# Gate-drive.net
KiCad netlist of a schematic drawn in Altium Designer
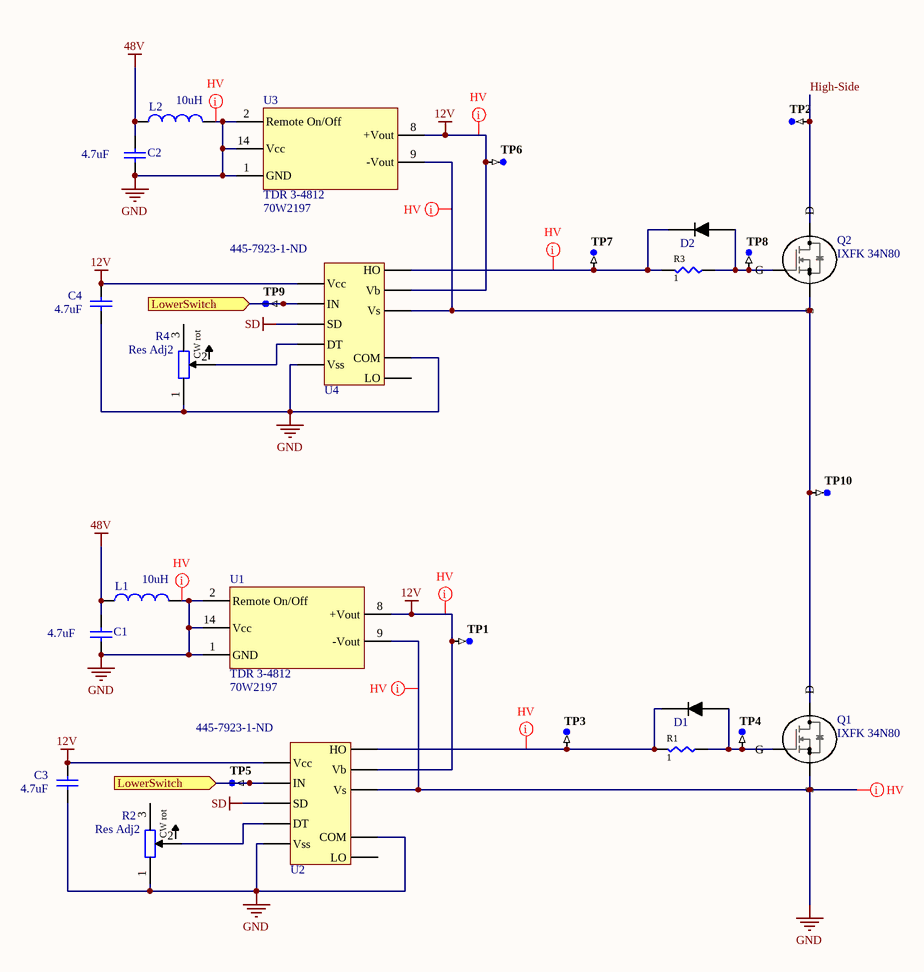
[diagram p0: Gate-drive.SchDoc]

(export (version "E")
  (design (tool "Eeschema 10.0.6"))
  (components
    (comp (ref "C1")
      (value "4.7uF")
      (footprint "C4532")
      (description "Capacitor")
      (fields
        (field (name "MANUFACTURER") "TDK")
        (field (name "MANUFACTURER PART NUMBER") "CGA8N3X7S2A475K230KB")
        (field (name "PUBLISHER") "Altium Limited")
      )
      (libsource (lib "T-Type Converter") (part "Cap"))
    )
    (comp (ref "C2")
      (value "4.7uF")
      (footprint "C4532")
      (description "Capacitor")
      (fields
        (field (name "MANUFACTURER") "TDK")
        (field (name "MANUFACTURER PART NUMBER") "CGA8N3X7S2A475K230KB")
        (field (name "PUBLISHER") "Altium Limited")
      )
      (libsource (lib "T-Type Converter") (part "Cap"))
    )
    (comp (ref "C3")
      (value "4.7uF")
      (footprint "C4532")
      (description "Capacitor")
      (fields
        (field (name "SUPPLIER PART NUMBER 1") "445-7923-1-ND")
        (field (name "MANUFACTURER") "TDK")
        (field (name "MANUFACTURER PART NUMBER") "CGA8N3X7S2A475K230KB")
        (field (name "PUBLISHER") "Altium Limited")
      )
      (libsource (lib "T-Type Converter") (part "Cap"))
    )
    (comp (ref "C4")
      (value "4.7uF")
      (footprint "C4532")
      (description "Capacitor")
      (fields
        (field (name "SUPPLIER PART NUMBER 1") "445-7923-1-ND")
        (field (name "MANUFACTURER") "TDK")
        (field (name "MANUFACTURER PART NUMBER") "CGA8N3X7S2A475K230KB")
        (field (name "PUBLISHER") "Altium Limited")
      )
      (libsource (lib "T-Type Converter") (part "Cap"))
    )
    (comp (ref "D1")
      (value "1N4148")
      (footprint "DO-35_02")
      (description "Diode")
      (fields (field (name "MANUFACTURER") "Fairchild Semiconductor"))
      (libsource (lib "T-Type Converter") (part "1N4148"))
    )
    (comp (ref "D2")
      (value "1N4148")
      (footprint "DO-35_02")
      (description "Diode")
      (fields (field (name "MANUFACTURER") "Fairchild Semiconductor"))
      (libsource (lib "T-Type Converter") (part "1N4148"))
    )
    (comp (ref "L1")
      (value "10uH")
      (footprint "TCK-047")
      (description "Inductor")
      (fields (field (name "PUBLISHER") "Altium Limited"))
      (libsource (lib "Miscellaneous Devices") (part "Inductor"))
    )
    (comp (ref "L2")
      (value "10uH")
      (footprint "TCK-047")
      (description "Inductor")
      (fields (field (name "PUBLISHER") "Altium Limited"))
      (libsource (lib "Miscellaneous Devices") (part "Inductor"))
    )
    (comp (ref "Q1")
      (value "IXFK 34N80")
      (footprint "TO-264 AA")
      (description "MOSFET 34A")
      (fields (field (name "MANUFACTURER") "IXYS") (field (name "MANUFACTURER PART NUMBER") "IXFK34N80"))
      (libsource (lib "T-Type Converter") (part "IXFK 34N80"))
    )
    (comp (ref "Q2")
      (value "IXFK 34N80")
      (footprint "TO-264 AA")
      (description "MOSFET 34A")
      (fields (field (name "MANUFACTURER") "IXYS") (field (name "MANUFACTURER PART NUMBER") "IXFK34N80"))
      (libsource (lib "T-Type Converter") (part "IXFK 34N80"))
    )
    (comp (ref "R1")
      (value "1")
      (footprint "R_1206")
      (description "RES SMD 1% 1/4W 1206")
      (fields
        (field (name "MANUFACTURER") "Panasonic Electronic Components")
        (field (name "MANUFACTURER PART NUMBER") "ERJ-8ENF9101V")
      )
      (libsource (lib "T-Type Converter") (part "RES_SMD1"))
    )
    (comp (ref "R2")
      (value "Res Adj2")
      (footprint "CT-6EP")
      (description "Variable Resistor")
      (fields
        (field (name "MANUFACTURER") "Nidec Copal")
        (field (name "MANUFACTURER PART NUMBER") "CT-6EP103")
        (field (name "PUBLISHER") "Altium Limited")
      )
      (libsource (lib "T-Type Converter") (part "Res Adj2"))
    )
    (comp (ref "R3")
      (value "1")
      (footprint "R_1206")
      (description "RES SMD 1% 1/4W 1206")
      (fields
        (field (name "MANUFACTURER") "Panasonic Electronic Components")
        (field (name "MANUFACTURER PART NUMBER") "ERJ-8ENF9101V")
      )
      (libsource (lib "T-Type Converter") (part "RES_SMD1"))
    )
    (comp (ref "R4")
      (value "Res Adj2")
      (footprint "CT-6EP")
      (description "Variable Resistor")
      (fields
        (field (name "MANUFACTURER") "Nidec Copal")
        (field (name "MANUFACTURER PART NUMBER") "CT-6EP103")
        (field (name "PUBLISHER") "Altium Limited")
      )
      (libsource (lib "T-Type Converter") (part "Res Adj2"))
    )
    (comp (ref "TP1")
      (value "TP-SM-C-100")
      (footprint "TP-SM-C-100")
      (description "Test Point, Surface Mount, Circular, Pad Diameter 1 mm")
      (fields (field (name "MANUFACTURER") "No Vendor"))
      (libsource (lib "Altium Content Vault") (part "CMP-0484-00002-2"))
    )
    (comp (ref "TP2")
      (value "TP-SM-C-100")
      (footprint "TP-SM-C-100")
      (description "Test Point, Surface Mount, Circular, Pad Diameter 1 mm")
      (fields (field (name "MANUFACTURER") "No Vendor"))
      (libsource (lib "Altium Content Vault") (part "CMP-0484-00002-2"))
    )
    (comp (ref "TP3")
      (value "TP-SM-C-100")
      (footprint "TP-SM-C-100")
      (description "Test Point, Surface Mount, Circular, Pad Diameter 1 mm")
      (fields (field (name "MANUFACTURER") "No Vendor"))
      (libsource (lib "Altium Content Vault") (part "CMP-0484-00002-2"))
    )
    (comp (ref "TP4")
      (value "TP-SM-C-100")
      (footprint "TP-SM-C-100")
      (description "Test Point, Surface Mount, Circular, Pad Diameter 1 mm")
      (fields (field (name "MANUFACTURER") "No Vendor"))
      (libsource (lib "Altium Content Vault") (part "CMP-0484-00002-2"))
    )
    (comp (ref "TP5")
      (value "TP-SM-C-100")
      (footprint "TP-SM-C-100")
      (description "Test Point, Surface Mount, Circular, Pad Diameter 1 mm")
      (fields (field (name "MANUFACTURER") "No Vendor"))
      (libsource (lib "Altium Content Vault") (part "CMP-0484-00002-2"))
    )
    (comp (ref "TP6")
      (value "TP-SM-C-100")
      (footprint "TP-SM-C-100")
      (description "Test Point, Surface Mount, Circular, Pad Diameter 1 mm")
      (fields (field (name "MANUFACTURER") "No Vendor"))
      (libsource (lib "Altium Content Vault") (part "CMP-0484-00002-2"))
    )
    (comp (ref "TP7")
      (value "TP-SM-C-100")
      (footprint "TP-SM-C-100")
      (description "Test Point, Surface Mount, Circular, Pad Diameter 1 mm")
      (fields (field (name "MANUFACTURER") "No Vendor"))
      (libsource (lib "Altium Content Vault") (part "CMP-0484-00002-2"))
    )
    (comp (ref "TP8")
      (value "TP-SM-C-100")
      (footprint "TP-SM-C-100")
      (description "Test Point, Surface Mount, Circular, Pad Diameter 1 mm")
      (fields (field (name "MANUFACTURER") "No Vendor"))
      (libsource (lib "Altium Content Vault") (part "CMP-0484-00002-2"))
    )
    (comp (ref "TP9")
      (value "TP-SM-C-100")
      (footprint "TP-SM-C-100")
      (description "Test Point, Surface Mount, Circular, Pad Diameter 1 mm")
      (fields (field (name "MANUFACTURER") "No Vendor"))
      (libsource (lib "Altium Content Vault") (part "CMP-0484-00002-2"))
    )
    (comp (ref "TP10")
      (value "TP-SM-C-100")
      (footprint "TP-SM-C-100")
      (description "Test Point, Surface Mount, Circular, Pad Diameter 1 mm")
      (fields (field (name "MANUFACTURER") "No Vendor"))
      (libsource (lib "Altium Content Vault") (part "CMP-0484-00002-2"))
    )
    (comp (ref "U1")
      (value "TDR 3-4812")
      (footprint "PID DC-DC Converter - duplicate")
      (description "48V-12V Converter")
      (fields
        (field (name "MANUFACTURER") "Traco Power")
        (field (name "MANUFACTURER PART NUMBER") "TDR3-4812WI")
        (field (name "SUPPLIER PART NUMBER 1") "70W2197")
      )
      (libsource (lib "T-Type Converter") (part "TDR 3-4812"))
    )
    (comp (ref "U2")
      (value "IR21094")
      (footprint "DIP14")
      (description "HALF-BRIDGE DRIVER")
      (libsource (lib "T-Type Converter") (part "IR21094"))
    )
    (comp (ref "U3")
      (value "TDR 3-4812")
      (footprint "PID DC-DC Converter - duplicate")
      (description "48V-12V Converter")
      (fields
        (field (name "MANUFACTURER") "Traco Power")
        (field (name "MANUFACTURER PART NUMBER") "TDR3-4812WI")
        (field (name "SUPPLIER PART NUMBER 1") "70W2197")
      )
      (libsource (lib "T-Type Converter") (part "TDR 3-4812"))
    )
    (comp (ref "U4")
      (value "IR21094")
      (footprint "DIP14")
      (description "HALF-BRIDGE DRIVER")
      (libsource (lib "T-Type Converter") (part "IR21094"))
    )
  )
  (nets
    (net (code "1") (name "/High-Side") (class "Default")
      (node (ref "Q2") (pin "2") (pinfunction "D_2") (pintype "passive"))
      (node (ref "TP2") (pin "1") (pinfunction "1_1") (pintype "input"))
    )
    (net (code "2") (name "/LowerSwitch") (class "Default")
      (node (ref "TP5") (pin "1") (pinfunction "1_1") (pintype "input"))
      (node (ref "TP9") (pin "1") (pinfunction "1_1") (pintype "input"))
      (node (ref "U2") (pin "2") (pinfunction "IN_2") (pintype "passive"))
      (node (ref "U4") (pin "2") (pinfunction "IN_2") (pintype "passive"))
    )
    (net (code "3") (name "12V") (class "Default")
      (node (ref "C3") (pin "2") (pinfunction "2_2") (pintype "passive"))
      (node (ref "C4") (pin "2") (pinfunction "2_2") (pintype "passive"))
      (node (ref "TP1") (pin "1") (pinfunction "1_1") (pintype "input"))
      (node (ref "TP6") (pin "1") (pinfunction "1_1") (pintype "input"))
      (node (ref "U1") (pin "8") (pinfunction "+Vout_8") (pintype "passive"))
      (node (ref "U2") (pin "1") (pinfunction "Vcc_1") (pintype "passive"))
      (node (ref "U2") (pin "13") (pinfunction "Vb_13") (pintype "passive"))
      (node (ref "U3") (pin "8") (pinfunction "+Vout_8") (pintype "passive"))
      (node (ref "U4") (pin "1") (pinfunction "Vcc_1") (pintype "passive"))
      (node (ref "U4") (pin "13") (pinfunction "Vb_13") (pintype "passive"))
    )
    (net (code "4") (name "48V") (class "Default")
      (node (ref "C1") (pin "2") (pinfunction "2_2") (pintype "passive"))
      (node (ref "C2") (pin "2") (pinfunction "2_2") (pintype "passive"))
      (node (ref "L1") (pin "1") (pinfunction "1_1") (pintype "passive"))
      (node (ref "L2") (pin "1") (pinfunction "1_1") (pintype "passive"))
    )
    (net (code "5") (name "GND") (class "Default")
      (node (ref "C1") (pin "1") (pinfunction "1_1") (pintype "passive"))
      (node (ref "C2") (pin "1") (pinfunction "1_1") (pintype "passive"))
      (node (ref "C3") (pin "1") (pinfunction "1_1") (pintype "passive"))
      (node (ref "C4") (pin "1") (pinfunction "1_1") (pintype "passive"))
      (node (ref "L1") (pin "2") (pinfunction "2_2") (pintype "passive"))
      (node (ref "L2") (pin "2") (pinfunction "2_2") (pintype "passive"))
      (node (ref "Q1") (pin "3") (pinfunction "S_3") (pintype "passive"))
      (node (ref "R2") (pin "1") (pintype "passive"))
      (node (ref "R4") (pin "1") (pintype "passive"))
      (node (ref "U1") (pin "1") (pinfunction "GND_1") (pintype "power_in"))
      (node (ref "U1") (pin "14") (pinfunction "Vcc_14") (pintype "passive"))
      (node (ref "U1") (pin "2") (pinfunction "Remote_On/Off_2") (pintype "passive"))
      (node (ref "U1") (pin "9") (pinfunction "-Vout_9") (pintype "passive"))
      (node (ref "U2") (pin "11") (pinfunction "Vs_11") (pintype "passive"))
      (node (ref "U2") (pin "5") (pinfunction "Vss_5") (pintype "passive"))
      (node (ref "U2") (pin "6") (pinfunction "COM_6") (pintype "passive"))
      (node (ref "U3") (pin "1") (pinfunction "GND_1") (pintype "power_in"))
      (node (ref "U3") (pin "14") (pinfunction "Vcc_14") (pintype "passive"))
      (node (ref "U3") (pin "2") (pinfunction "Remote_On/Off_2") (pintype "passive"))
      (node (ref "U4") (pin "5") (pinfunction "Vss_5") (pintype "passive"))
      (node (ref "U4") (pin "6") (pinfunction "COM_6") (pintype "passive"))
    )
    (net (code "6") (name "Net-(D1-Anode)") (class "Default")
      (node (ref "D1") (pin "2") (pinfunction "Anode_2") (pintype "passive"))
      (node (ref "Q1") (pin "1") (pinfunction "G_1") (pintype "passive"))
      (node (ref "R1") (pin "2") (pinfunction "2_2") (pintype "passive"))
      (node (ref "TP4") (pin "1") (pinfunction "1_1") (pintype "input"))
    )
    (net (code "7") (name "Net-(D1-Cathode)") (class "Default")
      (node (ref "D1") (pin "1") (pinfunction "Cathode_1") (pintype "passive"))
      (node (ref "R1") (pin "1") (pinfunction "1_1") (pintype "passive"))
      (node (ref "TP3") (pin "1") (pinfunction "1_1") (pintype "input"))
      (node (ref "U2") (pin "12") (pinfunction "HO_12") (pintype "passive"))
    )
    (net (code "8") (name "Net-(D2-Anode)") (class "Default")
      (node (ref "D2") (pin "2") (pinfunction "Anode_2") (pintype "passive"))
      (node (ref "Q2") (pin "1") (pinfunction "G_1") (pintype "passive"))
      (node (ref "R3") (pin "2") (pinfunction "2_2") (pintype "passive"))
      (node (ref "TP8") (pin "1") (pinfunction "1_1") (pintype "input"))
    )
    (net (code "9") (name "Net-(D2-Cathode)") (class "Default")
      (node (ref "D2") (pin "1") (pinfunction "Cathode_1") (pintype "passive"))
      (node (ref "R3") (pin "1") (pinfunction "1_1") (pintype "passive"))
      (node (ref "TP7") (pin "1") (pinfunction "1_1") (pintype "input"))
      (node (ref "U4") (pin "12") (pinfunction "HO_12") (pintype "passive"))
    )
    (net (code "10") (name "Net-(Q1-D)") (class "Default")
      (node (ref "Q1") (pin "2") (pinfunction "D_2") (pintype "passive"))
      (node (ref "Q2") (pin "3") (pinfunction "S_3") (pintype "passive"))
      (node (ref "TP10") (pin "1") (pinfunction "1_1") (pintype "input"))
      (node (ref "U3") (pin "9") (pinfunction "-Vout_9") (pintype "passive"))
      (node (ref "U4") (pin "11") (pinfunction "Vs_11") (pintype "passive"))
    )
    (net (code "11") (name "Net-(R2-3)") (class "Default")
      (node (ref "R2") (pin "2") (pinfunction "3_2") (pintype "passive"))
      (node (ref "U2") (pin "4") (pinfunction "DT_4") (pintype "passive"))
    )
    (net (code "12") (name "Net-(R4-3)") (class "Default")
      (node (ref "R4") (pin "2") (pinfunction "3_2") (pintype "passive"))
      (node (ref "U4") (pin "4") (pinfunction "DT_4") (pintype "passive"))
    )
    (net (code "13") (name "SD") (class "Default")
      (node (ref "U2") (pin "3") (pinfunction "SD_3") (pintype "passive"))
      (node (ref "U4") (pin "3") (pinfunction "SD_3") (pintype "passive"))
    )
    (net (code "14") (name "unconnected-(R2-Pad3)") (class "Default")
      (node (ref "R2") (pin "3") (pintype "passive"))
    )
    (net (code "15") (name "unconnected-(R4-Pad3)") (class "Default")
      (node (ref "R4") (pin "3") (pintype "passive"))
    )
    (net (code "16") (name "unconnected-(U2-LO-Pad7)") (class "Default")
      (node (ref "U2") (pin "7") (pinfunction "LO_7") (pintype "passive"))
    )
    (net (code "17") (name "unconnected-(U4-LO-Pad7)") (class "Default")
      (node (ref "U4") (pin "7") (pinfunction "LO_7") (pintype "passive"))
    )
  )
)
